# ADF_1st_mixer.net
KiCad netlist of a schematic drawn in Altium Designer
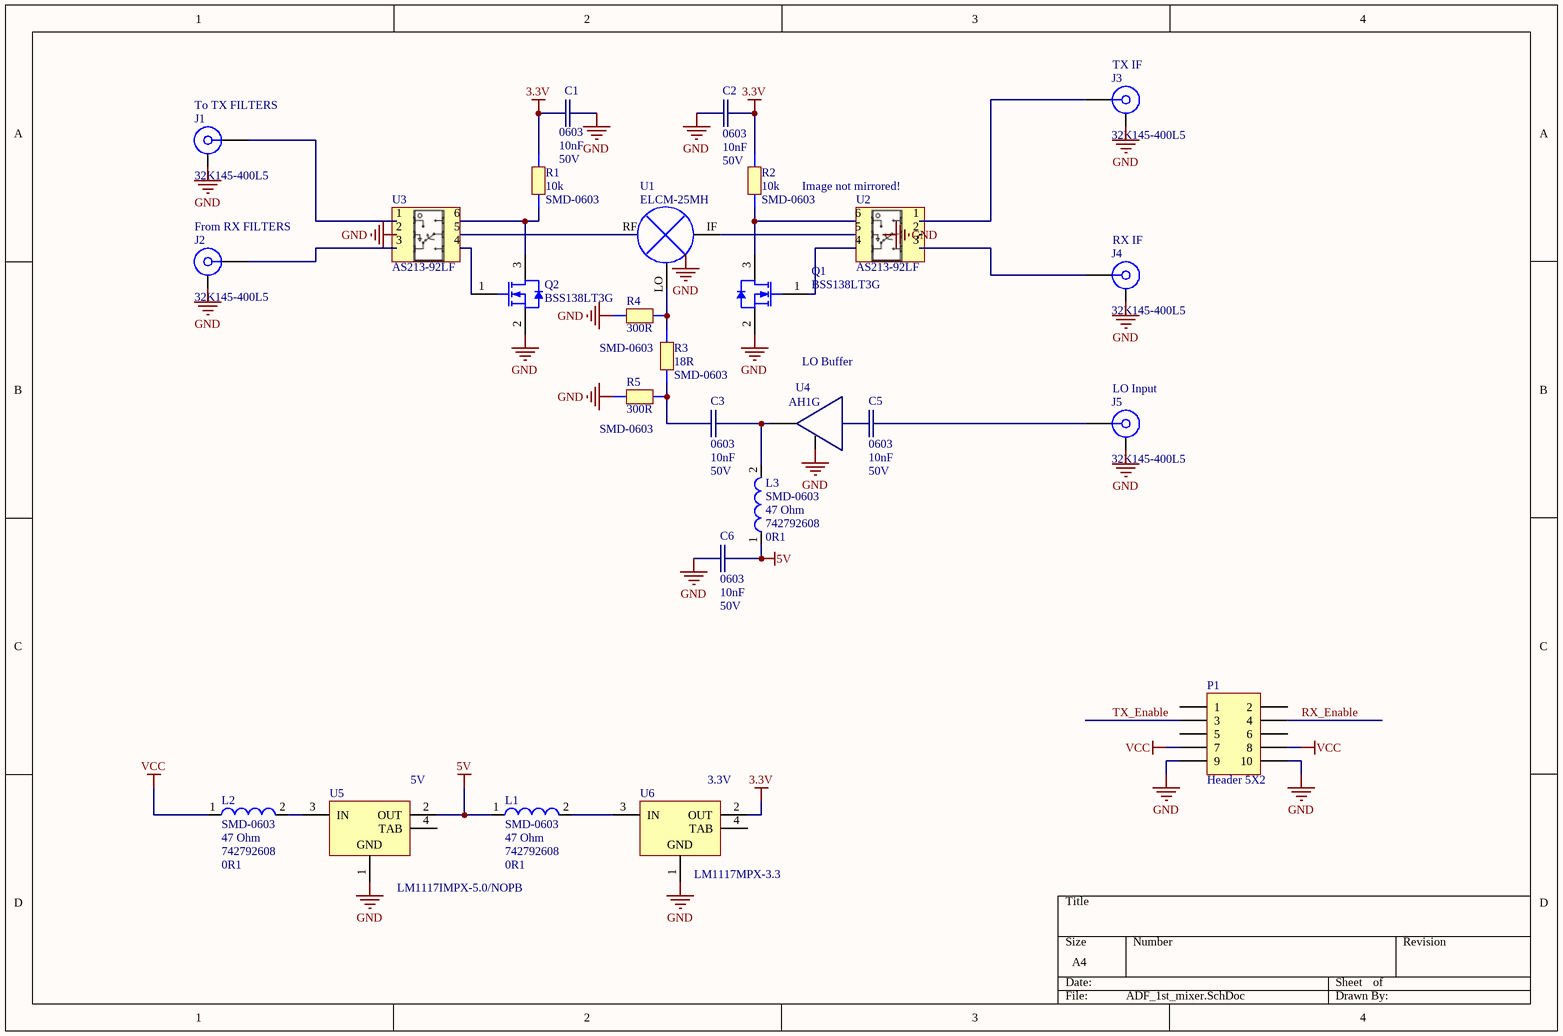
[diagram p0: ADF_1st_mixer.SchDoc]

(export (version "E")
  (design (tool "Eeschema 10.0.6"))
  (components
    (comp (ref "C1")
      (value "10nF 0603 NP0")
      (footprint "C0603_murata")
      (description "10nF 0603 NP0 muRata")
      (fields
        (field (name "TOLERANCE") "5%")
        (field (name "CASE CODE (IMPERIAL)") "0603")
        (field (name "CAPACITANCE") "10nF")
        (field (name "VOLTAGE") "50V")
      )
      (libsource (lib "ftg_lib") (part "10nF 0603 NP0"))
    )
    (comp (ref "C2")
      (value "10nF 0603 NP0")
      (footprint "C0603_murata")
      (description "10nF 0603 NP0 muRata")
      (fields
        (field (name "TOLERANCE") "5%")
        (field (name "CASE CODE (IMPERIAL)") "0603")
        (field (name "CAPACITANCE") "10nF")
        (field (name "VOLTAGE") "50V")
      )
      (libsource (lib "ftg_lib") (part "10nF 0603 NP0"))
    )
    (comp (ref "C3")
      (value "10nF 0603 NP0")
      (footprint "C0603_murata")
      (description "10nF 0603 NP0 muRata")
      (fields
        (field (name "TOLERANCE") "5%")
        (field (name "CASE CODE (IMPERIAL)") "0603")
        (field (name "CAPACITANCE") "10nF")
        (field (name "VOLTAGE") "50V")
      )
      (libsource (lib "ftg_lib") (part "10nF 0603 NP0"))
    )
    (comp (ref "C5")
      (value "10nF 0603 NP0")
      (footprint "C0603_murata")
      (description "10nF 0603 NP0 muRata")
      (fields
        (field (name "TOLERANCE") "5%")
        (field (name "CASE CODE (IMPERIAL)") "0603")
        (field (name "CAPACITANCE") "10nF")
        (field (name "VOLTAGE") "50V")
      )
      (libsource (lib "ftg_lib") (part "10nF 0603 NP0"))
    )
    (comp (ref "C6")
      (value "10nF 0603 NP0")
      (footprint "C0603_murata")
      (description "10nF 0603 NP0 muRata")
      (fields
        (field (name "TOLERANCE") "5%")
        (field (name "CASE CODE (IMPERIAL)") "0603")
        (field (name "CAPACITANCE") "10nF")
        (field (name "VOLTAGE") "50V")
      )
      (libsource (lib "ftg_lib") (part "10nF 0603 NP0"))
    )
    (comp (ref "J1")
      (value "32K145-400L5")
      (footprint "ROS-32K145-400L5_V")
      (description "SMA Right Angle Jack, Edge Mount, Up to 18 GHz, -55 to 155 degC")
      (libsource (lib "Rosenberger SMA") (part "32K145-400L5"))
    )
    (comp (ref "J2")
      (value "32K145-400L5")
      (footprint "ROS-32K145-400L5_V")
      (description "SMA Right Angle Jack, Edge Mount, Up to 18 GHz, -55 to 155 degC")
      (libsource (lib "Rosenberger SMA") (part "32K145-400L5"))
    )
    (comp (ref "J3")
      (value "32K145-400L5")
      (footprint "ROS-32K145-400L5_V")
      (description "SMA Right Angle Jack, Edge Mount, Up to 18 GHz, -55 to 155 degC")
      (libsource (lib "Rosenberger SMA") (part "32K145-400L5"))
    )
    (comp (ref "J4")
      (value "32K145-400L5")
      (footprint "ROS-32K145-400L5_V")
      (description "SMA Right Angle Jack, Edge Mount, Up to 18 GHz, -55 to 155 degC")
      (libsource (lib "Rosenberger SMA") (part "32K145-400L5"))
    )
    (comp (ref "J5")
      (value "32K145-400L5")
      (footprint "ROS-32K145-400L5_V")
      (description "SMA Right Angle Jack, Edge Mount, Up to 18 GHz, -55 to 155 degC")
      (libsource (lib "Rosenberger SMA") (part "32K145-400L5"))
    )
    (comp (ref "L1")
      (value "742792608")
      (footprint "SMD-0603")
      (description "SMD EMI Suppression Ferrite Bead WE-CBF, Z = 47 Ohm")
      (fields
        (field (name "PACKAGEREFERENCE") "SMD-0603")
        (field (name "IMPEDANCE") "47 Ohm")
        (field (name "DC_RESISTANCE") "0R1")
      )
      (libsource (lib "AQA_20007_4_Flange") (part "742792608"))
    )
    (comp (ref "L2")
      (value "742792608")
      (footprint "SMD-0603")
      (description "SMD EMI Suppression Ferrite Bead WE-CBF, Z = 47 Ohm")
      (fields
        (field (name "PACKAGEREFERENCE") "SMD-0603")
        (field (name "IMPEDANCE") "47 Ohm")
        (field (name "DC_RESISTANCE") "0R1")
      )
      (libsource (lib "AQA_20007_4_Flange") (part "742792608"))
    )
    (comp (ref "L3")
      (value "742792608")
      (footprint "SMD-0603")
      (description "SMD EMI Suppression Ferrite Bead WE-CBF, Z = 47 Ohm")
      (fields
        (field (name "PACKAGEREFERENCE") "SMD-0603")
        (field (name "IMPEDANCE") "47 Ohm")
        (field (name "DC_RESISTANCE") "0R1")
      )
      (libsource (lib "AQA_20007_4_Flange") (part "742792608"))
    )
    (comp (ref "P1")
      (value "Header 5X2")
      (footprint "HDR2X5")
      (description "Header, 5-Pin, Dual row")
      (fields (field (name "PUBLISHER") "Altium Limited"))
      (libsource (lib "Miscellaneous Connectors") (part "Header 5X2"))
    )
    (comp (ref "Q1")
      (value "BSS138LT3G")
      (footprint "ONSC-SOT-23-3-318-08_V")
      (description "Power MOSFET, 200 mA, 50 V, N-Channel, 3-Pin SOT-23, Pb-Free, Tape and Reel")
      (fields (field (name "MANUFACTURER") "On Semiconductor"))
      (libsource (lib "Altium Content Vault") (part "ONSC-NMOS-G1S2D3-3"))
    )
    (comp (ref "Q2")
      (value "BSS138LT3G")
      (footprint "ONSC-SOT-23-3-318-08_V")
      (description "Power MOSFET, 200 mA, 50 V, N-Channel, 3-Pin SOT-23, Pb-Free, Tape and Reel")
      (fields (field (name "MANUFACTURER") "On Semiconductor"))
      (libsource (lib "Altium Content Vault") (part "CMP-1058-00765-1"))
    )
    (comp (ref "R1")
      (value "10k")
      (footprint "RESC1608X06N_0603")
      (description "Generic SMD Resistor")
      (fields
        (field (name "MANUFACTURER") "SUSUMU")
        (field (name "VOLTAGE") "75V")
        (field (name "PACKAGEREFERENCE") "SMD-0603")
        (field (name "PUBLISHER") "atr")
      )
      (libsource (lib "AQA_atr_2013") (part "Resistor_SMD_Generic"))
    )
    (comp (ref "R2")
      (value "10k")
      (footprint "RESC1608X06N_0603")
      (description "Generic SMD Resistor")
      (fields
        (field (name "MANUFACTURER") "SUSUMU")
        (field (name "VOLTAGE") "75V")
        (field (name "PACKAGEREFERENCE") "SMD-0603")
        (field (name "PUBLISHER") "atr")
      )
      (libsource (lib "AQA_atr_2013") (part "Resistor_SMD_Generic"))
    )
    (comp (ref "R3")
      (value "18R")
      (footprint "RESC1608X06N_0603")
      (description "Bulk SMD Resistor")
      (fields
        (field (name "MANUFACTURER") "PANASONIC")
        (field (name "VOLTAGE") "75V")
        (field (name "PACKAGEREFERENCE") "SMD-0603")
        (field (name "PUBLISHER") "atr")
      )
      (libsource (lib "") (part "Resistor_0R_0603_Bulk_1"))
    )
    (comp (ref "R4")
      (value "300R")
      (footprint "RESC1608X06N_0603")
      (description "Bulk SMD Resistor")
      (fields
        (field (name "MANUFACTURER") "PANASONIC")
        (field (name "VOLTAGE") "75V")
        (field (name "PACKAGEREFERENCE") "SMD-0603")
        (field (name "PUBLISHER") "atr")
      )
      (libsource (lib "AQA_atr_2013") (part "Resistor_0R_0603_Bulk"))
    )
    (comp (ref "R5")
      (value "300R")
      (footprint "RESC1608X06N_0603")
      (description "Bulk SMD Resistor")
      (fields
        (field (name "MANUFACTURER") "PANASONIC")
        (field (name "VOLTAGE") "75V")
        (field (name "PACKAGEREFERENCE") "SMD-0603")
        (field (name "PUBLISHER") "atr")
      )
      (libsource (lib "AQA_atr_2013") (part "Resistor_0R_0603_Bulk"))
    )
    (comp (ref "U1") (value "ELCM-25MH") (footprint "SM-87") (libsource (lib "ftg_lib") (part "ELCM-25MH")))
    (comp (ref "U2")
      (value "AS213-92LF")
      (footprint "SC70_6")
      (description "Switch SPDT 0.1-3GHZ GAAS SC70-6")
      (libsource (lib "") (part "AS213-92LF_1"))
    )
    (comp (ref "U3")
      (value "AS213-92LF")
      (footprint "SC70_6")
      (description "Switch SPDT 0.1-3GHZ GAAS SC70-6")
      (libsource (lib "ftg_lib") (part "AS213-92LF"))
    )
    (comp (ref "U4")
      (value "AH1G")
      (footprint "SOT-89")
      (description "250-4000MHz MMIC")
      (libsource (lib "ftg_lib") (part "AH1G"))
    )
    (comp (ref "U5")
      (value "LM1117IMPX-5.0/NOPB")
      (footprint "MP04A_L")
      (description "800mA Low-Dropout Linear Regulator, 4-pin SOT-223, Pb-Free")
      (fields (field (name "MANUFACTURER") "National Semiconductor"))
      (libsource (lib "Altium Content Vault") (part "PM-REG-LM1086-SOT4"))
    )
    (comp (ref "U6")
      (value "LM1117MPX-3.3")
      (footprint "DCY0004A_M")
      (description "800mA Low-Dropout Linear Regulator, 4-pin SOT-223")
      (fields (field (name "MANUFACTURER") "Texas Instruments"))
      (libsource (lib "Altium Content Vault") (part "PM-REG-LM1086-SOT4"))
    )
  )
  (nets
    (net (code "1") (name "/RX_Enable") (class "Default")
      (node (ref "P1") (pin "4") (pinfunction "4_4") (pintype "passive"))
    )
    (net (code "2") (name "/TX_Enable") (class "Default")
      (node (ref "P1") (pin "3") (pinfunction "3_3") (pintype "passive"))
    )
    (net (code "3") (name "3.3V") (class "Default")
      (node (ref "C1") (pin "1") (pinfunction "1_1") (pintype "passive"))
      (node (ref "C2") (pin "2") (pinfunction "2_2") (pintype "passive"))
      (node (ref "R1") (pin "2") (pinfunction "2_2") (pintype "passive"))
      (node (ref "R2") (pin "2") (pinfunction "2_2") (pintype "passive"))
      (node (ref "U6") (pin "2") (pinfunction "OUT_2") (pintype "power_in"))
    )
    (net (code "4") (name "5V") (class "Default")
      (node (ref "C6") (pin "2") (pinfunction "2_2") (pintype "passive"))
      (node (ref "L1") (pin "1") (pinfunction "1_1") (pintype "passive"))
      (node (ref "L3") (pin "1") (pinfunction "1_1") (pintype "passive"))
      (node (ref "U5") (pin "2") (pinfunction "OUT_2") (pintype "power_in"))
    )
    (net (code "5") (name "GND") (class "Default")
      (node (ref "C1") (pin "2") (pinfunction "2_2") (pintype "passive"))
      (node (ref "C2") (pin "1") (pinfunction "1_1") (pintype "passive"))
      (node (ref "C6") (pin "1") (pinfunction "1_1") (pintype "passive"))
      (node (ref "J1") (pin "MP") (pinfunction "MP_MP") (pintype "passive"))
      (node (ref "J2") (pin "MP") (pinfunction "MP_MP") (pintype "passive"))
      (node (ref "J3") (pin "MP") (pinfunction "MP_MP") (pintype "passive"))
      (node (ref "J4") (pin "MP") (pinfunction "MP_MP") (pintype "passive"))
      (node (ref "J5") (pin "MP") (pinfunction "MP_MP") (pintype "passive"))
      (node (ref "P1") (pin "10") (pinfunction "10_10") (pintype "passive"))
      (node (ref "P1") (pin "9") (pinfunction "9_9") (pintype "passive"))
      (node (ref "Q1") (pin "2") (pinfunction "S_2") (pintype "passive"))
      (node (ref "Q2") (pin "2") (pinfunction "S_2") (pintype "passive"))
      (node (ref "R4") (pin "2") (pinfunction "2_2") (pintype "passive"))
      (node (ref "R5") (pin "2") (pinfunction "2_2") (pintype "passive"))
      (node (ref "U1") (pin "GND") (pinfunction "GND_GND") (pintype "passive"))
      (node (ref "U3") (pin "2") (pinfunction "2_2") (pintype "passive"))
      (node (ref "U4") (pin "2") (pinfunction "2_2") (pintype "passive"))
      (node (ref "U5") (pin "1") (pinfunction "GND_1") (pintype "power_in"))
      (node (ref "U6") (pin "1") (pinfunction "GND_1") (pintype "power_in"))
    )
    (net (code "6") (name "Net-(C3-Pad1)") (class "Default")
      (node (ref "C3") (pin "1") (pinfunction "1_1") (pintype "passive"))
      (node (ref "R3") (pin "1") (pinfunction "1_1") (pintype "passive"))
      (node (ref "R5") (pin "1") (pinfunction "1_1") (pintype "passive"))
    )
    (net (code "7") (name "Net-(C3-Pad2)") (class "Default")
      (node (ref "C3") (pin "2") (pinfunction "2_2") (pintype "passive"))
      (node (ref "L3") (pin "2") (pinfunction "2_2") (pintype "passive"))
      (node (ref "U4") (pin "3") (pinfunction "3_3") (pintype "passive"))
    )
    (net (code "8") (name "Net-(C5-Pad1)") (class "Default")
      (node (ref "C5") (pin "1") (pinfunction "1_1") (pintype "passive"))
      (node (ref "U4") (pin "1") (pinfunction "1_1") (pintype "passive"))
    )
    (net (code "9") (name "Net-(C5-Pad2)") (class "Default")
      (node (ref "C5") (pin "2") (pinfunction "2_2") (pintype "passive"))
      (node (ref "J5") (pin "1") (pinfunction "1_1") (pintype "passive"))
    )
    (net (code "10") (name "Net-(J1-Pad1)") (class "Default")
      (node (ref "J1") (pin "1") (pinfunction "1_1") (pintype "passive"))
      (node (ref "U3") (pin "1") (pinfunction "1_1") (pintype "passive"))
    )
    (net (code "11") (name "Net-(J2-Pad1)") (class "Default")
      (node (ref "J2") (pin "1") (pinfunction "1_1") (pintype "passive"))
      (node (ref "U3") (pin "3") (pinfunction "3_3") (pintype "passive"))
    )
    (net (code "12") (name "Net-(J3-Pad1)") (class "Default")
      (node (ref "J3") (pin "1") (pinfunction "1_1") (pintype "passive"))
      (node (ref "U2") (pin "1") (pinfunction "1_1") (pintype "passive"))
    )
    (net (code "13") (name "Net-(J4-Pad1)") (class "Default")
      (node (ref "J4") (pin "1") (pinfunction "1_1") (pintype "passive"))
      (node (ref "U2") (pin "3") (pinfunction "3_3") (pintype "passive"))
    )
    (net (code "14") (name "Net-(Q1-D)") (class "Default")
      (node (ref "Q1") (pin "3") (pinfunction "D_3") (pintype "passive"))
      (node (ref "R2") (pin "1") (pinfunction "1_1") (pintype "passive"))
      (node (ref "U2") (pin "6") (pinfunction "6_6") (pintype "passive"))
    )
    (net (code "15") (name "Net-(Q1-G)") (class "Default")
      (node (ref "Q1") (pin "1") (pinfunction "G_1") (pintype "passive"))
      (node (ref "U2") (pin "4") (pinfunction "4_4") (pintype "passive"))
    )
    (net (code "16") (name "Net-(Q2-D)") (class "Default")
      (node (ref "Q2") (pin "3") (pinfunction "D_3") (pintype "passive"))
      (node (ref "R1") (pin "1") (pinfunction "1_1") (pintype "passive"))
      (node (ref "U3") (pin "6") (pinfunction "6_6") (pintype "passive"))
    )
    (net (code "17") (name "Net-(Q2-G)") (class "Default")
      (node (ref "Q2") (pin "1") (pinfunction "G_1") (pintype "passive"))
      (node (ref "U3") (pin "4") (pinfunction "4_4") (pintype "passive"))
    )
    (net (code "18") (name "Net-(R3-Pad2)") (class "Default")
      (node (ref "R3") (pin "2") (pinfunction "2_2") (pintype "passive"))
      (node (ref "R4") (pin "1") (pinfunction "1_1") (pintype "passive"))
      (node (ref "U1") (pin "LO") (pinfunction "LO_LO") (pintype "passive"))
    )
    (net (code "19") (name "Net-(U1-PadIF)") (class "Default")
      (node (ref "U1") (pin "IF") (pinfunction "IF_IF") (pintype "passive"))
      (node (ref "U2") (pin "5") (pinfunction "5_5") (pintype "passive"))
    )
    (net (code "20") (name "Net-(U1-PadRF)") (class "Default")
      (node (ref "U1") (pin "RF") (pinfunction "RF_RF") (pintype "passive"))
      (node (ref "U3") (pin "5") (pinfunction "5_5") (pintype "passive"))
    )
    (net (code "21") (name "Net-(U5-IN)") (class "Default")
      (node (ref "L2") (pin "2") (pinfunction "2_2") (pintype "passive"))
      (node (ref "U5") (pin "3") (pinfunction "IN_3") (pintype "power_in"))
    )
    (net (code "22") (name "Net-(U6-IN)") (class "Default")
      (node (ref "L1") (pin "2") (pinfunction "2_2") (pintype "passive"))
      (node (ref "U6") (pin "3") (pinfunction "IN_3") (pintype "power_in"))
    )
    (net (code "23") (name "VCC") (class "Default")
      (node (ref "L2") (pin "1") (pinfunction "1_1") (pintype "passive"))
      (node (ref "P1") (pin "7") (pinfunction "7_7") (pintype "passive"))
      (node (ref "P1") (pin "8") (pinfunction "8_8") (pintype "passive"))
    )
    (net (code "24") (name "unconnected-(P1-Pad1)") (class "Default")
      (node (ref "P1") (pin "1") (pinfunction "1_1") (pintype "passive"))
    )
    (net (code "25") (name "unconnected-(P1-Pad2)") (class "Default")
      (node (ref "P1") (pin "2") (pinfunction "2_2") (pintype "passive"))
    )
    (net (code "26") (name "unconnected-(P1-Pad5)") (class "Default")
      (node (ref "P1") (pin "5") (pinfunction "5_5") (pintype "passive"))
    )
    (net (code "27") (name "unconnected-(P1-Pad6)") (class "Default")
      (node (ref "P1") (pin "6") (pinfunction "6_6") (pintype "passive"))
    )
    (net (code "28") (name "unconnected-(U2-Pad2)") (class "Default")
      (node (ref "U2") (pin "2") (pinfunction "2_2") (pintype "passive"))
    )
    (net (code "29") (name "unconnected-(U5-TAB-Pad4)") (class "Default")
      (node (ref "U5") (pin "4") (pinfunction "TAB_4") (pintype "power_in"))
    )
    (net (code "30") (name "unconnected-(U6-TAB-Pad4)") (class "Default")
      (node (ref "U6") (pin "4") (pinfunction "TAB_4") (pintype "power_in"))
    )
  )
)
